# AC_light.net
KiCad netlist of a schematic drawn in EAGLE
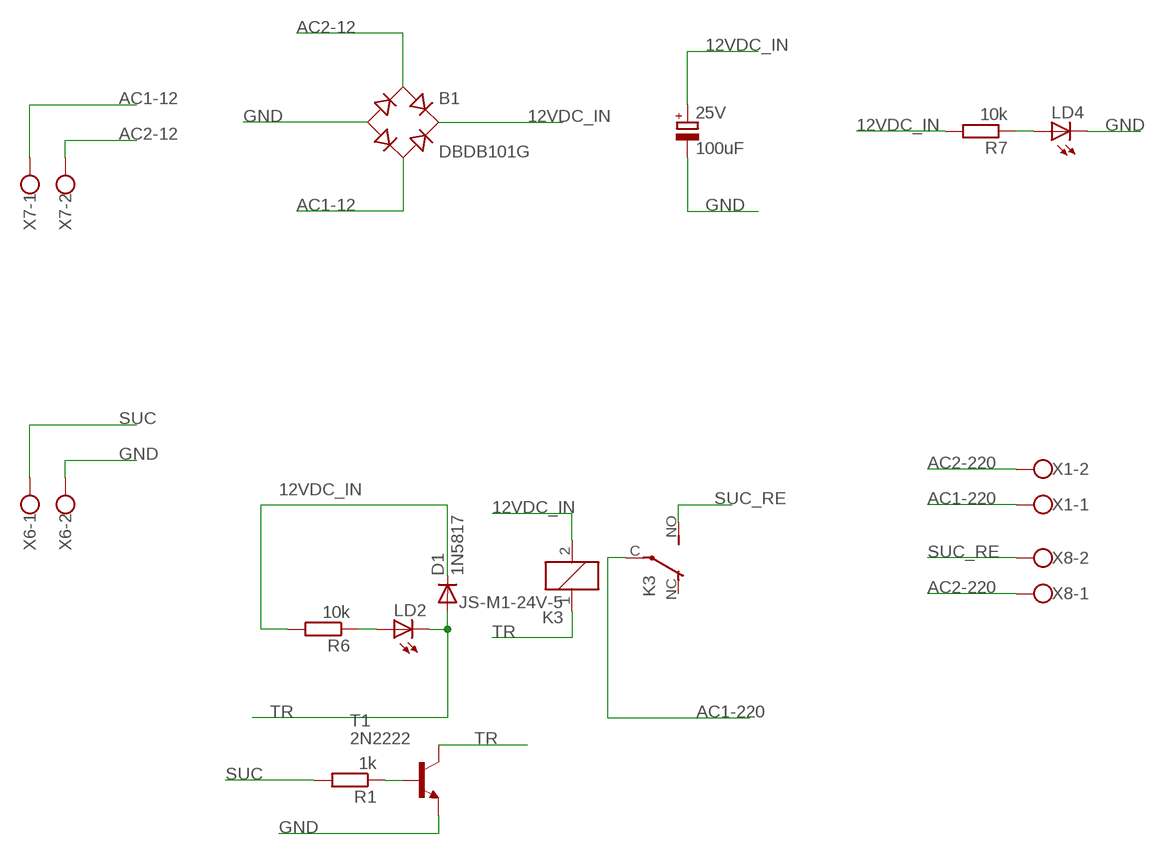
[diagram p0: schematic, sheet 1]

(export (version "E")
  (design (tool "Eeschema 10.0.6"))
  (components
    (comp (ref "25V")
      (value "100uF")
      (footprint "eagle-import:E3,5-8")
      (libsource (lib "eagle-import") (part "CPOL-EUE3.5-8"))
    )
    (comp (ref "B1")
      (value "DBDB101G")
      (footprint "eagle-import:DB")
      (libsource (lib "eagle-import") (part "DB?GDB101"))
    )
    (comp (ref "D1")
      (value "1N5817")
      (footprint "eagle-import:DO41-10")
      (libsource (lib "eagle-import") (part "1N4004"))
    )
    (comp (ref "K3")
      (value "JS-M1-24V-5")
      (footprint "eagle-import:JS-M")
      (fields (field (name "MF") "FARNELL") (field (name "MPN") "JSM1-12V-5"))
      (libsource (lib "eagle-import") (part "JS-M1-12V-5"))
    )
    (comp (ref "LD2")
      (value "LED5MM")
      (footprint "eagle-import:LED5MM")
      (libsource (lib "eagle-import") (part "LED5MM"))
    )
    (comp (ref "LD4")
      (value "LED5MM")
      (footprint "eagle-import:LED5MM")
      (libsource (lib "eagle-import") (part "LED5MM"))
    )
    (comp (ref "R1")
      (value "1k")
      (footprint "eagle-import:0207_10")
      (libsource (lib "eagle-import") (part "R-EU_0207/10"))
    )
    (comp (ref "R6")
      (value "10k")
      (footprint "eagle-import:0207_10")
      (libsource (lib "eagle-import") (part "R-EU_0207/10"))
    )
    (comp (ref "R7")
      (value "10k")
      (footprint "eagle-import:0207_10")
      (libsource (lib "eagle-import") (part "R-EU_0207/10"))
    )
    (comp (ref "T1")
      (value "2N2222")
      (footprint "eagle-import:TO92-EBC-OVAL")
      (libsource (lib "eagle-import") (part "2N2222"))
    )
    (comp (ref "X1")
      (value "W237-102")
      (footprint "eagle-import:W237-102")
      (libsource (lib "eagle-import") (part "W237-102"))
    )
    (comp (ref "X6")
      (value "W237-102")
      (footprint "eagle-import:W237-102")
      (libsource (lib "eagle-import") (part "W237-102"))
    )
    (comp (ref "X7")
      (value "W237-102")
      (footprint "eagle-import:W237-102")
      (libsource (lib "eagle-import") (part "W237-102"))
    )
    (comp (ref "X8")
      (value "W237-102")
      (footprint "eagle-import:W237-102")
      (libsource (lib "eagle-import") (part "W237-102"))
    )
  )
  (nets
    (net (code "1") (name "/12VDC_IN") (class "Default")
      (node (ref "25V") (pin "+") (pinfunction "+_+") (pintype "passive"))
      (node (ref "B1") (pin "+") (pinfunction "+_+") (pintype "passive"))
      (node (ref "D1") (pin "C") (pinfunction "C_C") (pintype "passive"))
      (node (ref "K3") (pin "2") (pinfunction "2_2") (pintype "passive"))
      (node (ref "R6") (pin "2") (pinfunction "2_2") (pintype "passive"))
      (node (ref "R7") (pin "2") (pinfunction "2_2") (pintype "passive"))
    )
    (net (code "2") (name "/AC1-12") (class "Default")
      (node (ref "B1") (pin "AC2") (pinfunction "AC2_AC2") (pintype "passive"))
      (node (ref "X7") (pin "1") (pinfunction "KL_1") (pintype "passive"))
    )
    (net (code "3") (name "/AC1-220") (class "Default")
      (node (ref "K3") (pin "C") (pinfunction "P_C") (pintype "passive"))
      (node (ref "X1") (pin "1") (pinfunction "KL_1") (pintype "passive"))
    )
    (net (code "4") (name "/AC2-12") (class "Default")
      (node (ref "B1") (pin "AC1") (pinfunction "AC1_AC1") (pintype "passive"))
      (node (ref "X7") (pin "2") (pinfunction "KL_2") (pintype "passive"))
    )
    (net (code "5") (name "/AC2-220") (class "Default")
      (node (ref "X1") (pin "2") (pinfunction "KL_2") (pintype "passive"))
      (node (ref "X8") (pin "1") (pinfunction "KL_1") (pintype "passive"))
    )
    (net (code "6") (name "/GND") (class "Default")
      (node (ref "25V") (pin "-") (pinfunction "-_-") (pintype "passive"))
      (node (ref "B1") (pin "-") (pinfunction "-_-") (pintype "passive"))
      (node (ref "LD4") (pin "K") (pinfunction "C_K") (pintype "passive"))
      (node (ref "T1") (pin "E") (pinfunction "E_E") (pintype "passive"))
      (node (ref "X6") (pin "2") (pinfunction "KL_2") (pintype "passive"))
    )
    (net (code "7") (name "/SUC") (class "Default")
      (node (ref "R1") (pin "2") (pinfunction "2_2") (pintype "passive"))
      (node (ref "X6") (pin "1") (pinfunction "KL_1") (pintype "passive"))
    )
    (net (code "8") (name "/SUC_RE") (class "Default")
      (node (ref "K3") (pin "NO") (pinfunction "S_NO") (pintype "passive"))
      (node (ref "X8") (pin "2") (pinfunction "KL_2") (pintype "passive"))
    )
    (net (code "9") (name "/TR") (class "Default")
      (node (ref "D1") (pin "A") (pinfunction "A_A") (pintype "passive"))
      (node (ref "K3") (pin "1") (pinfunction "1_1") (pintype "passive"))
      (node (ref "LD2") (pin "K") (pinfunction "C_K") (pintype "passive"))
      (node (ref "T1") (pin "C") (pinfunction "C_C") (pintype "passive"))
    )
    (net (code "10") (name "Net-(LD2-PadA)") (class "Default")
      (node (ref "LD2") (pin "A") (pinfunction "A_A") (pintype "passive"))
      (node (ref "R6") (pin "1") (pinfunction "1_1") (pintype "passive"))
    )
    (net (code "11") (name "Net-(LD4-PadA)") (class "Default")
      (node (ref "LD4") (pin "A") (pinfunction "A_A") (pintype "passive"))
      (node (ref "R7") (pin "1") (pinfunction "1_1") (pintype "passive"))
    )
    (net (code "12") (name "Net-(R1-Pad1)") (class "Default")
      (node (ref "R1") (pin "1") (pinfunction "1_1") (pintype "passive"))
      (node (ref "T1") (pin "B") (pinfunction "B_B") (pintype "passive"))
    )
    (net (code "13") (name "unconnected-(K3B-O-PadNC)") (class "Default")
      (node (ref "K3") (pin "NC") (pinfunction "O_NC") (pintype "passive"))
    )
  )
)
